# S_B_block_base.net
KiCad netlist of a schematic drawn in EAGLE
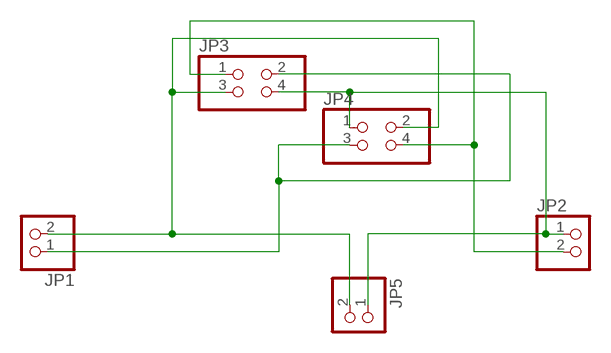
[diagram p0: schematic, sheet 1]

(export (version "E")
  (design (tool "Eeschema 10.0.6"))
  (components
    (comp (ref "JP1")
      (value "PINHD-1X2")
      (footprint "eagle-import:1X02")
      (libsource (lib "eagle-import") (part "PINHD-1X2"))
    )
    (comp (ref "JP2")
      (value "PINHD-1X2")
      (footprint "eagle-import:1X02")
      (libsource (lib "eagle-import") (part "PINHD-1X2"))
    )
    (comp (ref "JP3")
      (value "PINHD-2X2")
      (footprint "eagle-import:2X02")
      (libsource (lib "eagle-import") (part "PINHD-2X2"))
    )
    (comp (ref "JP4")
      (value "PINHD-2X2")
      (footprint "eagle-import:2X02")
      (libsource (lib "eagle-import") (part "PINHD-2X2"))
    )
    (comp (ref "JP5")
      (value "PINHD-1X2")
      (footprint "eagle-import:1X02")
      (libsource (lib "eagle-import") (part "PINHD-1X2"))
    )
  )
  (nets
    (net (code "1") (name "Net-(JP1-Pad1)") (class "Default")
      (node (ref "JP1") (pin "1") (pinfunction "1_1") (pintype "passive"))
      (node (ref "JP3") (pin "2") (pinfunction "2_2") (pintype "passive"))
      (node (ref "JP4") (pin "3") (pinfunction "3_3") (pintype "passive"))
    )
    (net (code "2") (name "Net-(JP1-Pad2)") (class "Default")
      (node (ref "JP1") (pin "2") (pinfunction "2_2") (pintype "passive"))
      (node (ref "JP3") (pin "3") (pinfunction "3_3") (pintype "passive"))
      (node (ref "JP4") (pin "2") (pinfunction "2_2") (pintype "passive"))
      (node (ref "JP5") (pin "2") (pinfunction "2_2") (pintype "passive"))
    )
    (net (code "3") (name "Net-(JP2-Pad1)") (class "Default")
      (node (ref "JP2") (pin "1") (pinfunction "1_1") (pintype "passive"))
      (node (ref "JP3") (pin "4") (pinfunction "4_4") (pintype "passive"))
      (node (ref "JP4") (pin "1") (pinfunction "1_1") (pintype "passive"))
      (node (ref "JP5") (pin "1") (pinfunction "1_1") (pintype "passive"))
    )
    (net (code "4") (name "Net-(JP2-Pad2)") (class "Default")
      (node (ref "JP2") (pin "2") (pinfunction "2_2") (pintype "passive"))
      (node (ref "JP3") (pin "1") (pinfunction "1_1") (pintype "passive"))
      (node (ref "JP4") (pin "4") (pinfunction "4_4") (pintype "passive"))
    )
  )
)
